# busbar.net
KiCad netlist of a schematic drawn in EAGLE
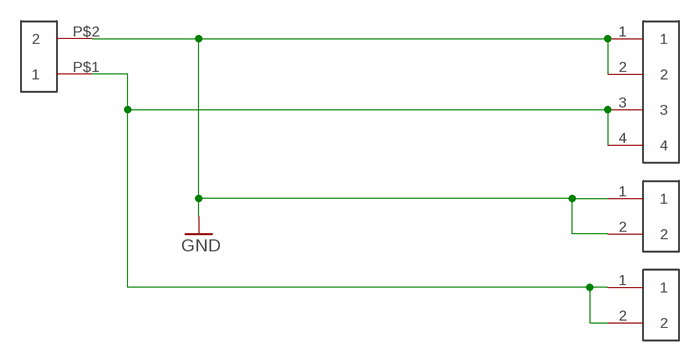
[diagram p0: schematic, sheet 1]

(export (version "E")
  (design (tool "Eeschema 10.0.6"))
  (components
    (comp (ref "U$1")
      (value "MOLEX-0436500200")
      (footprint "eagle-import:MOLEX_MICROFIT-2")
      (libsource (lib "eagle-import") (part "MOLEX-0436500200"))
    )
    (comp (ref "U$2")
      (value "1X4_HEADER")
      (footprint "eagle-import:1X4-.1HEADER")
      (libsource (lib "eagle-import") (part "1X4_HEADER"))
    )
    (comp (ref "U$3")
      (value "1X2_HEADER")
      (footprint "eagle-import:1X2-.1HEADER")
      (libsource (lib "eagle-import") (part "1X2_HEADER"))
    )
    (comp (ref "U$4")
      (value "1X2_HEADER")
      (footprint "eagle-import:1X2-.1HEADER")
      (libsource (lib "eagle-import") (part "1X2_HEADER"))
    )
  )
  (nets
    (net (code "1") (name "GND") (class "Default")
      (node (ref "U$1") (pin "P$2") (pinfunction "2_P$2") (pintype "bidirectional"))
      (node (ref "U$2") (pin "1") (pinfunction "1_1") (pintype "bidirectional"))
      (node (ref "U$2") (pin "2") (pinfunction "2_2") (pintype "bidirectional"))
      (node (ref "U$3") (pin "1") (pinfunction "1_1") (pintype "bidirectional"))
      (node (ref "U$3") (pin "2") (pinfunction "2_2") (pintype "bidirectional"))
    )
    (net (code "2") (name "Net-(U$1-1)") (class "Default")
      (node (ref "U$1") (pin "P$1") (pinfunction "1_P$1") (pintype "bidirectional"))
      (node (ref "U$2") (pin "3") (pinfunction "3_3") (pintype "bidirectional"))
      (node (ref "U$2") (pin "4") (pinfunction "4_4") (pintype "bidirectional"))
      (node (ref "U$4") (pin "1") (pinfunction "1_1") (pintype "bidirectional"))
      (node (ref "U$4") (pin "2") (pinfunction "2_2") (pintype "bidirectional"))
    )
  )
)
